# main.net
KiCad netlist of a schematic drawn in Altium Designer
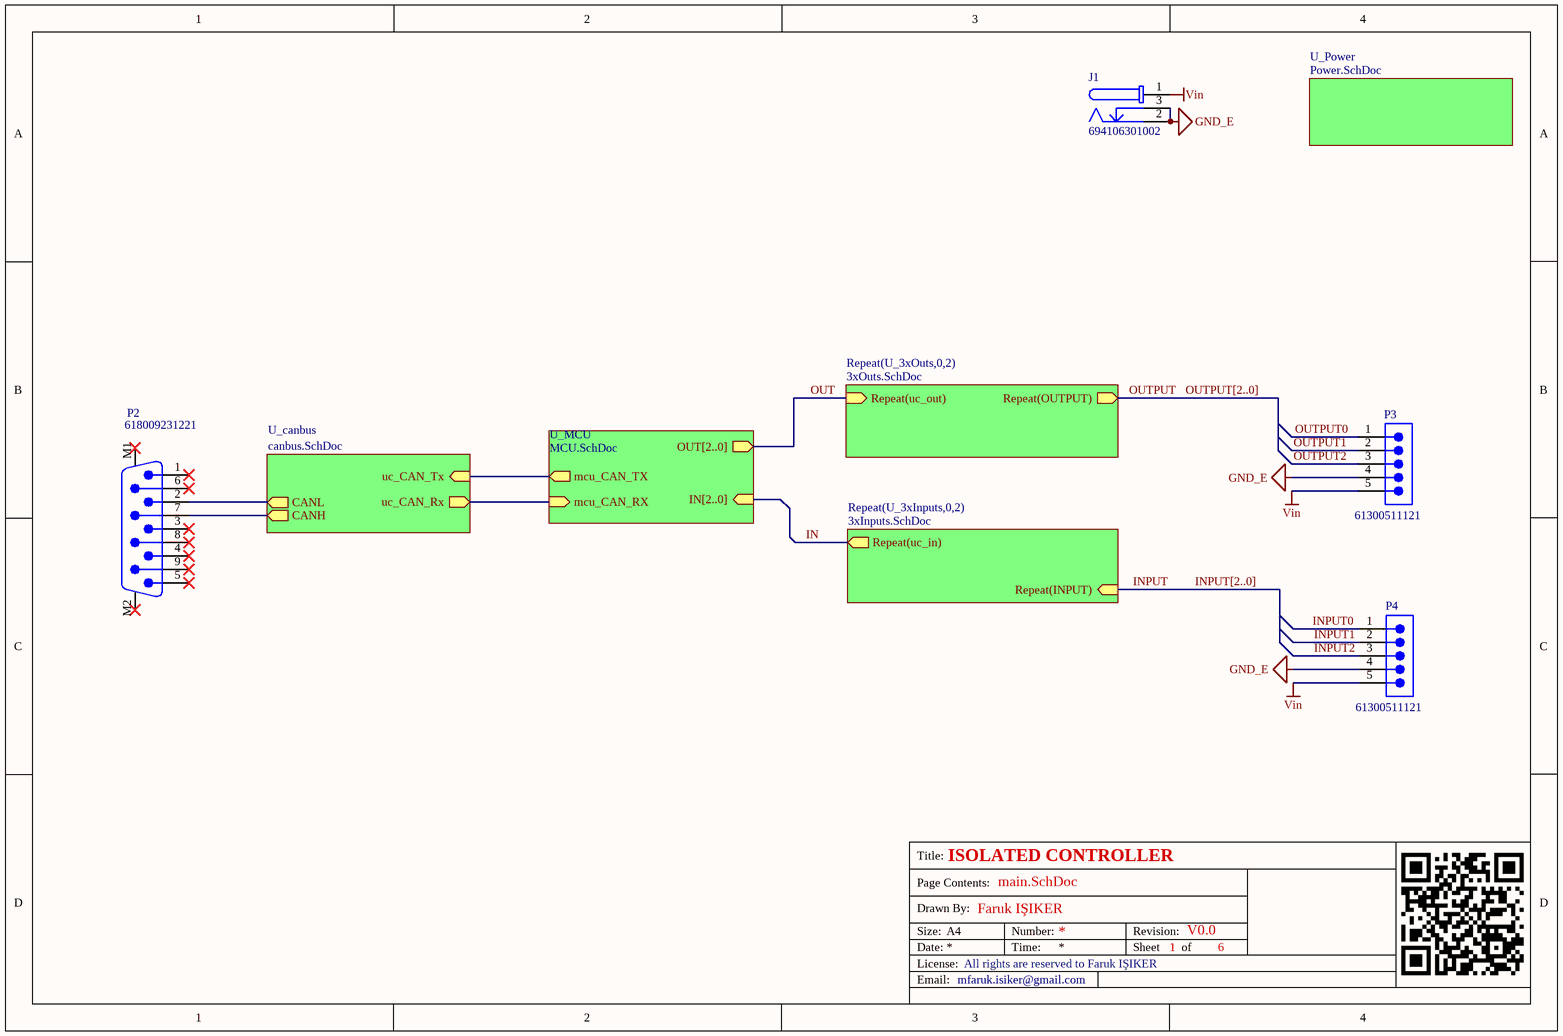
[diagram p0: main.SchDoc]

(export (version "E")
  (design (tool "Eeschema 10.0.6"))
  (components
    (comp (ref "J1")
      (value "694106301002")
      (footprint "694106301002")
      (libsource (lib "Altium Content Vault") (part "DC Power Jack"))
    )
    (comp (ref "P2")
      (value "618009231221")
      (footprint "618009231221")
      (libsource (lib "Altium Content Vault") (part "D-Sub_Male_09p"))
    )
    (comp (ref "P3")
      (value "61300511121")
      (footprint "61300511121")
      (libsource (lib "Altium Content Vault") (part "Header_Male_1R_05P"))
    )
    (comp (ref "P4")
      (value "61300511121")
      (footprint "61300511121")
      (libsource (lib "Altium Content Vault") (part "Header_Male_1R_05P"))
    )
  )
  (nets
    (net (code "1") (name "/CANH") (class "Default")
      (node (ref "P2") (pin "7") (pinfunction "7_7") (pintype "passive"))
    )
    (net (code "2") (name "/CANL") (class "Default")
      (node (ref "P2") (pin "2") (pinfunction "2_2") (pintype "passive"))
    )
    (net (code "5") (name "/INPUT0") (class "Default")
      (node (ref "P4") (pin "1") (pinfunction "1_1") (pintype "passive"))
    )
    (net (code "6") (name "/INPUT1") (class "Default")
      (node (ref "P4") (pin "2") (pinfunction "2_2") (pintype "passive"))
    )
    (net (code "7") (name "/INPUT2") (class "Default")
      (node (ref "P4") (pin "3") (pinfunction "3_3") (pintype "passive"))
    )
    (net (code "12") (name "/OUTPUT0") (class "Default")
      (node (ref "P3") (pin "1") (pinfunction "1_1") (pintype "passive"))
    )
    (net (code "13") (name "/OUTPUT1") (class "Default")
      (node (ref "P3") (pin "2") (pinfunction "2_2") (pintype "passive"))
    )
    (net (code "14") (name "/OUTPUT2") (class "Default")
      (node (ref "P3") (pin "3") (pinfunction "3_3") (pintype "passive"))
    )
    (net (code "19") (name "GND_E") (class "Default")
      (node (ref "J1") (pin "2") (pinfunction "2_2") (pintype "passive"))
      (node (ref "J1") (pin "3") (pinfunction "3_3") (pintype "passive"))
      (node (ref "P3") (pin "4") (pinfunction "4_4") (pintype "passive"))
      (node (ref "P4") (pin "4") (pinfunction "4_4") (pintype "passive"))
    )
    (net (code "20") (name "Vin") (class "Default")
      (node (ref "J1") (pin "1") (pinfunction "1_1") (pintype "passive"))
      (node (ref "P3") (pin "5") (pinfunction "5_5") (pintype "passive"))
      (node (ref "P4") (pin "5") (pinfunction "5_5") (pintype "passive"))
    )
    (net (code "21") (name "unconnected-(P2-Pad1)") (class "Default")
      (node (ref "P2") (pin "1") (pinfunction "1_1") (pintype "passive+no_connect"))
    )
    (net (code "22") (name "unconnected-(P2-Pad3)") (class "Default")
      (node (ref "P2") (pin "3") (pinfunction "3_3") (pintype "passive+no_connect"))
    )
    (net (code "23") (name "unconnected-(P2-Pad4)") (class "Default")
      (node (ref "P2") (pin "4") (pinfunction "4_4") (pintype "passive+no_connect"))
    )
    (net (code "24") (name "unconnected-(P2-Pad5)") (class "Default")
      (node (ref "P2") (pin "5") (pinfunction "5_5") (pintype "passive+no_connect"))
    )
    (net (code "25") (name "unconnected-(P2-Pad6)") (class "Default")
      (node (ref "P2") (pin "6") (pinfunction "6_6") (pintype "passive+no_connect"))
    )
    (net (code "26") (name "unconnected-(P2-Pad8)") (class "Default")
      (node (ref "P2") (pin "8") (pinfunction "8_8") (pintype "passive+no_connect"))
    )
    (net (code "27") (name "unconnected-(P2-Pad9)") (class "Default")
      (node (ref "P2") (pin "9") (pinfunction "9_9") (pintype "passive+no_connect"))
    )
    (net (code "28") (name "unconnected-(P2-PadM1)") (class "Default")
      (node (ref "P2") (pin "M1") (pinfunction "M1_M1") (pintype "passive+no_connect"))
    )
    (net (code "29") (name "unconnected-(P2-PadM2)") (class "Default")
      (node (ref "P2") (pin "M2") (pinfunction "M2_M2") (pintype "passive+no_connect"))
    )
  )
)
